# Adafruit_PyPortal_Pynt.net
KiCad netlist of a schematic drawn in EAGLE
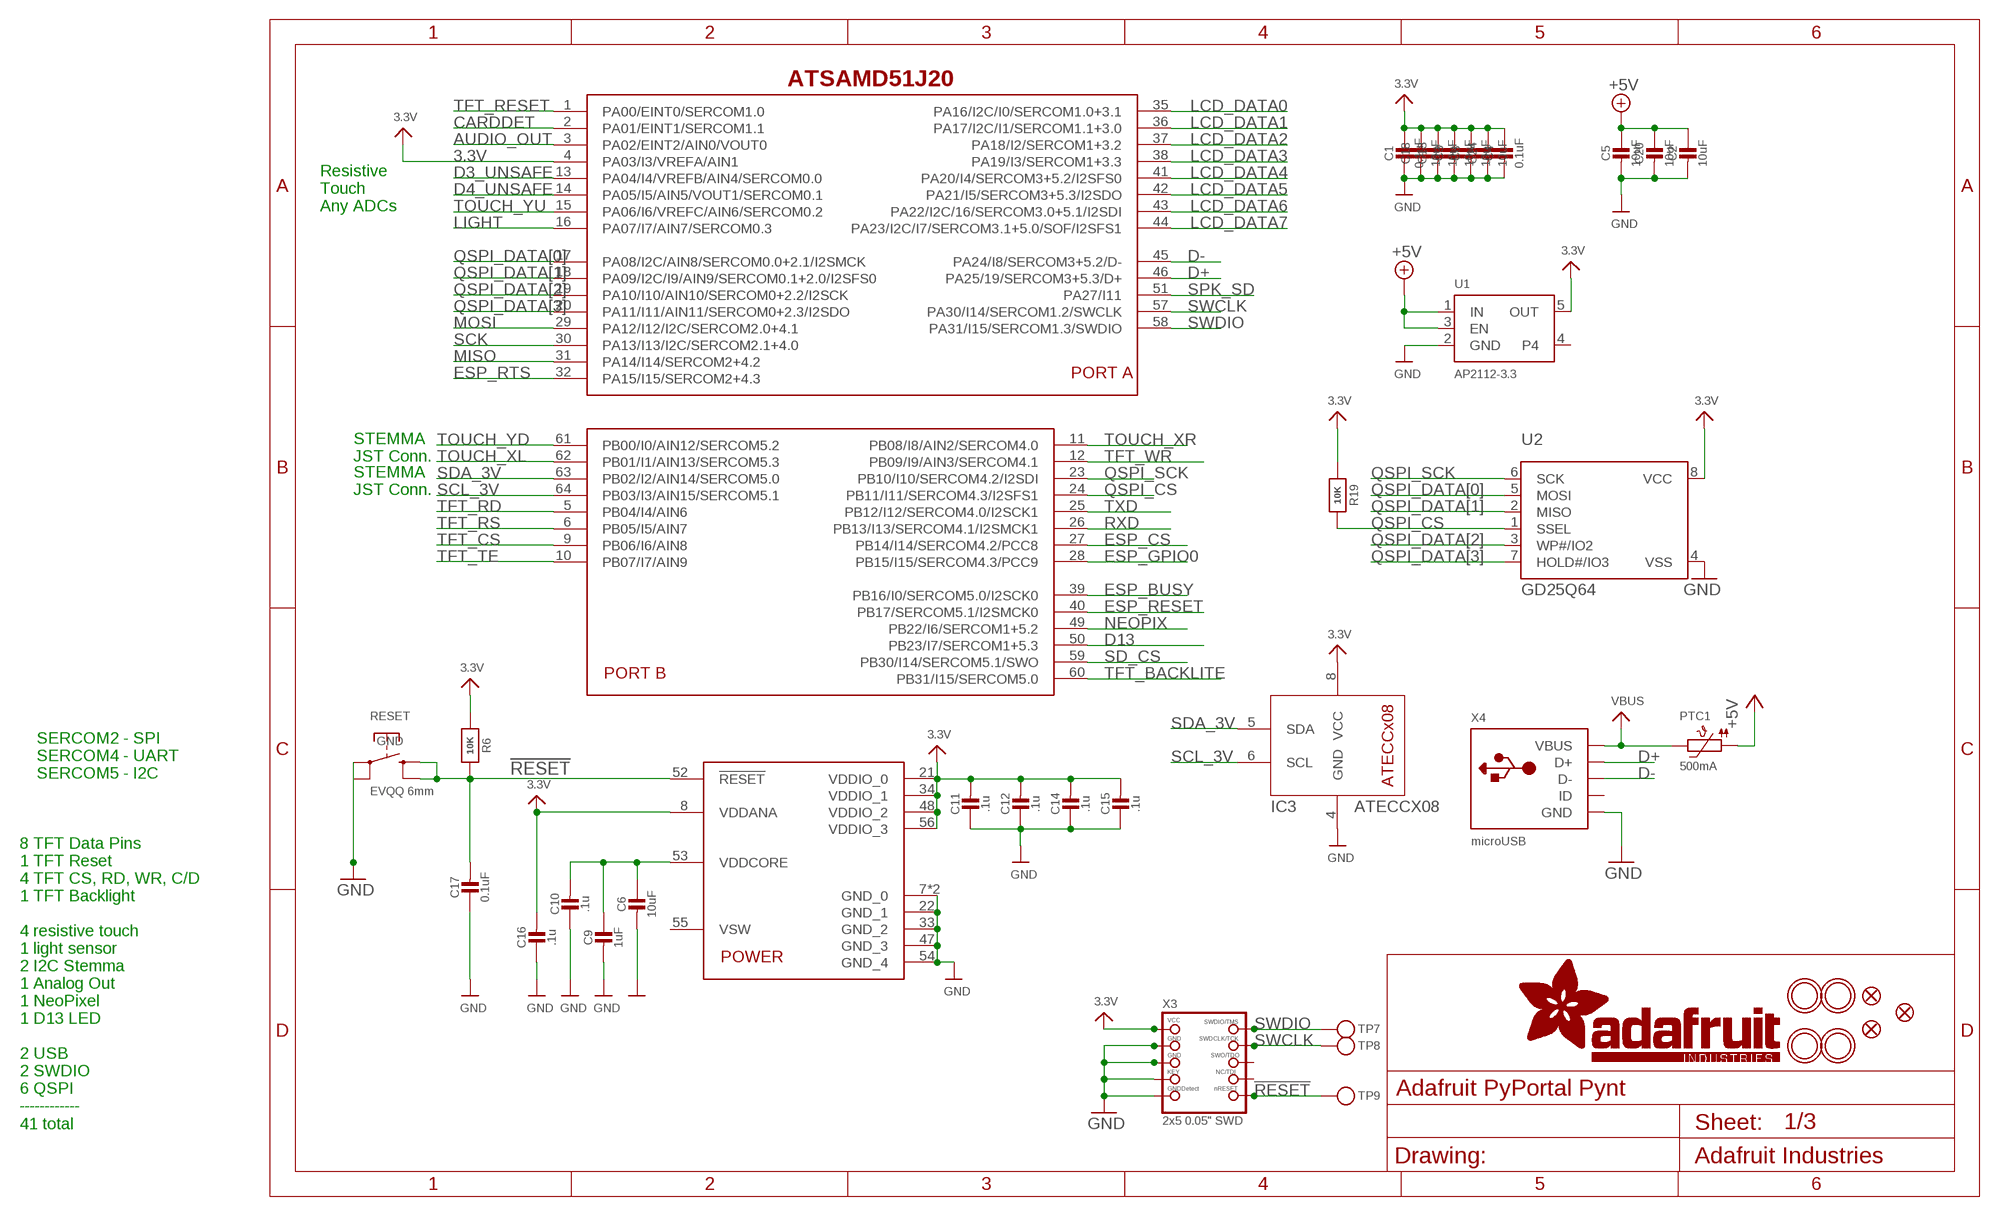
[diagram p0: schematic, sheet 1]
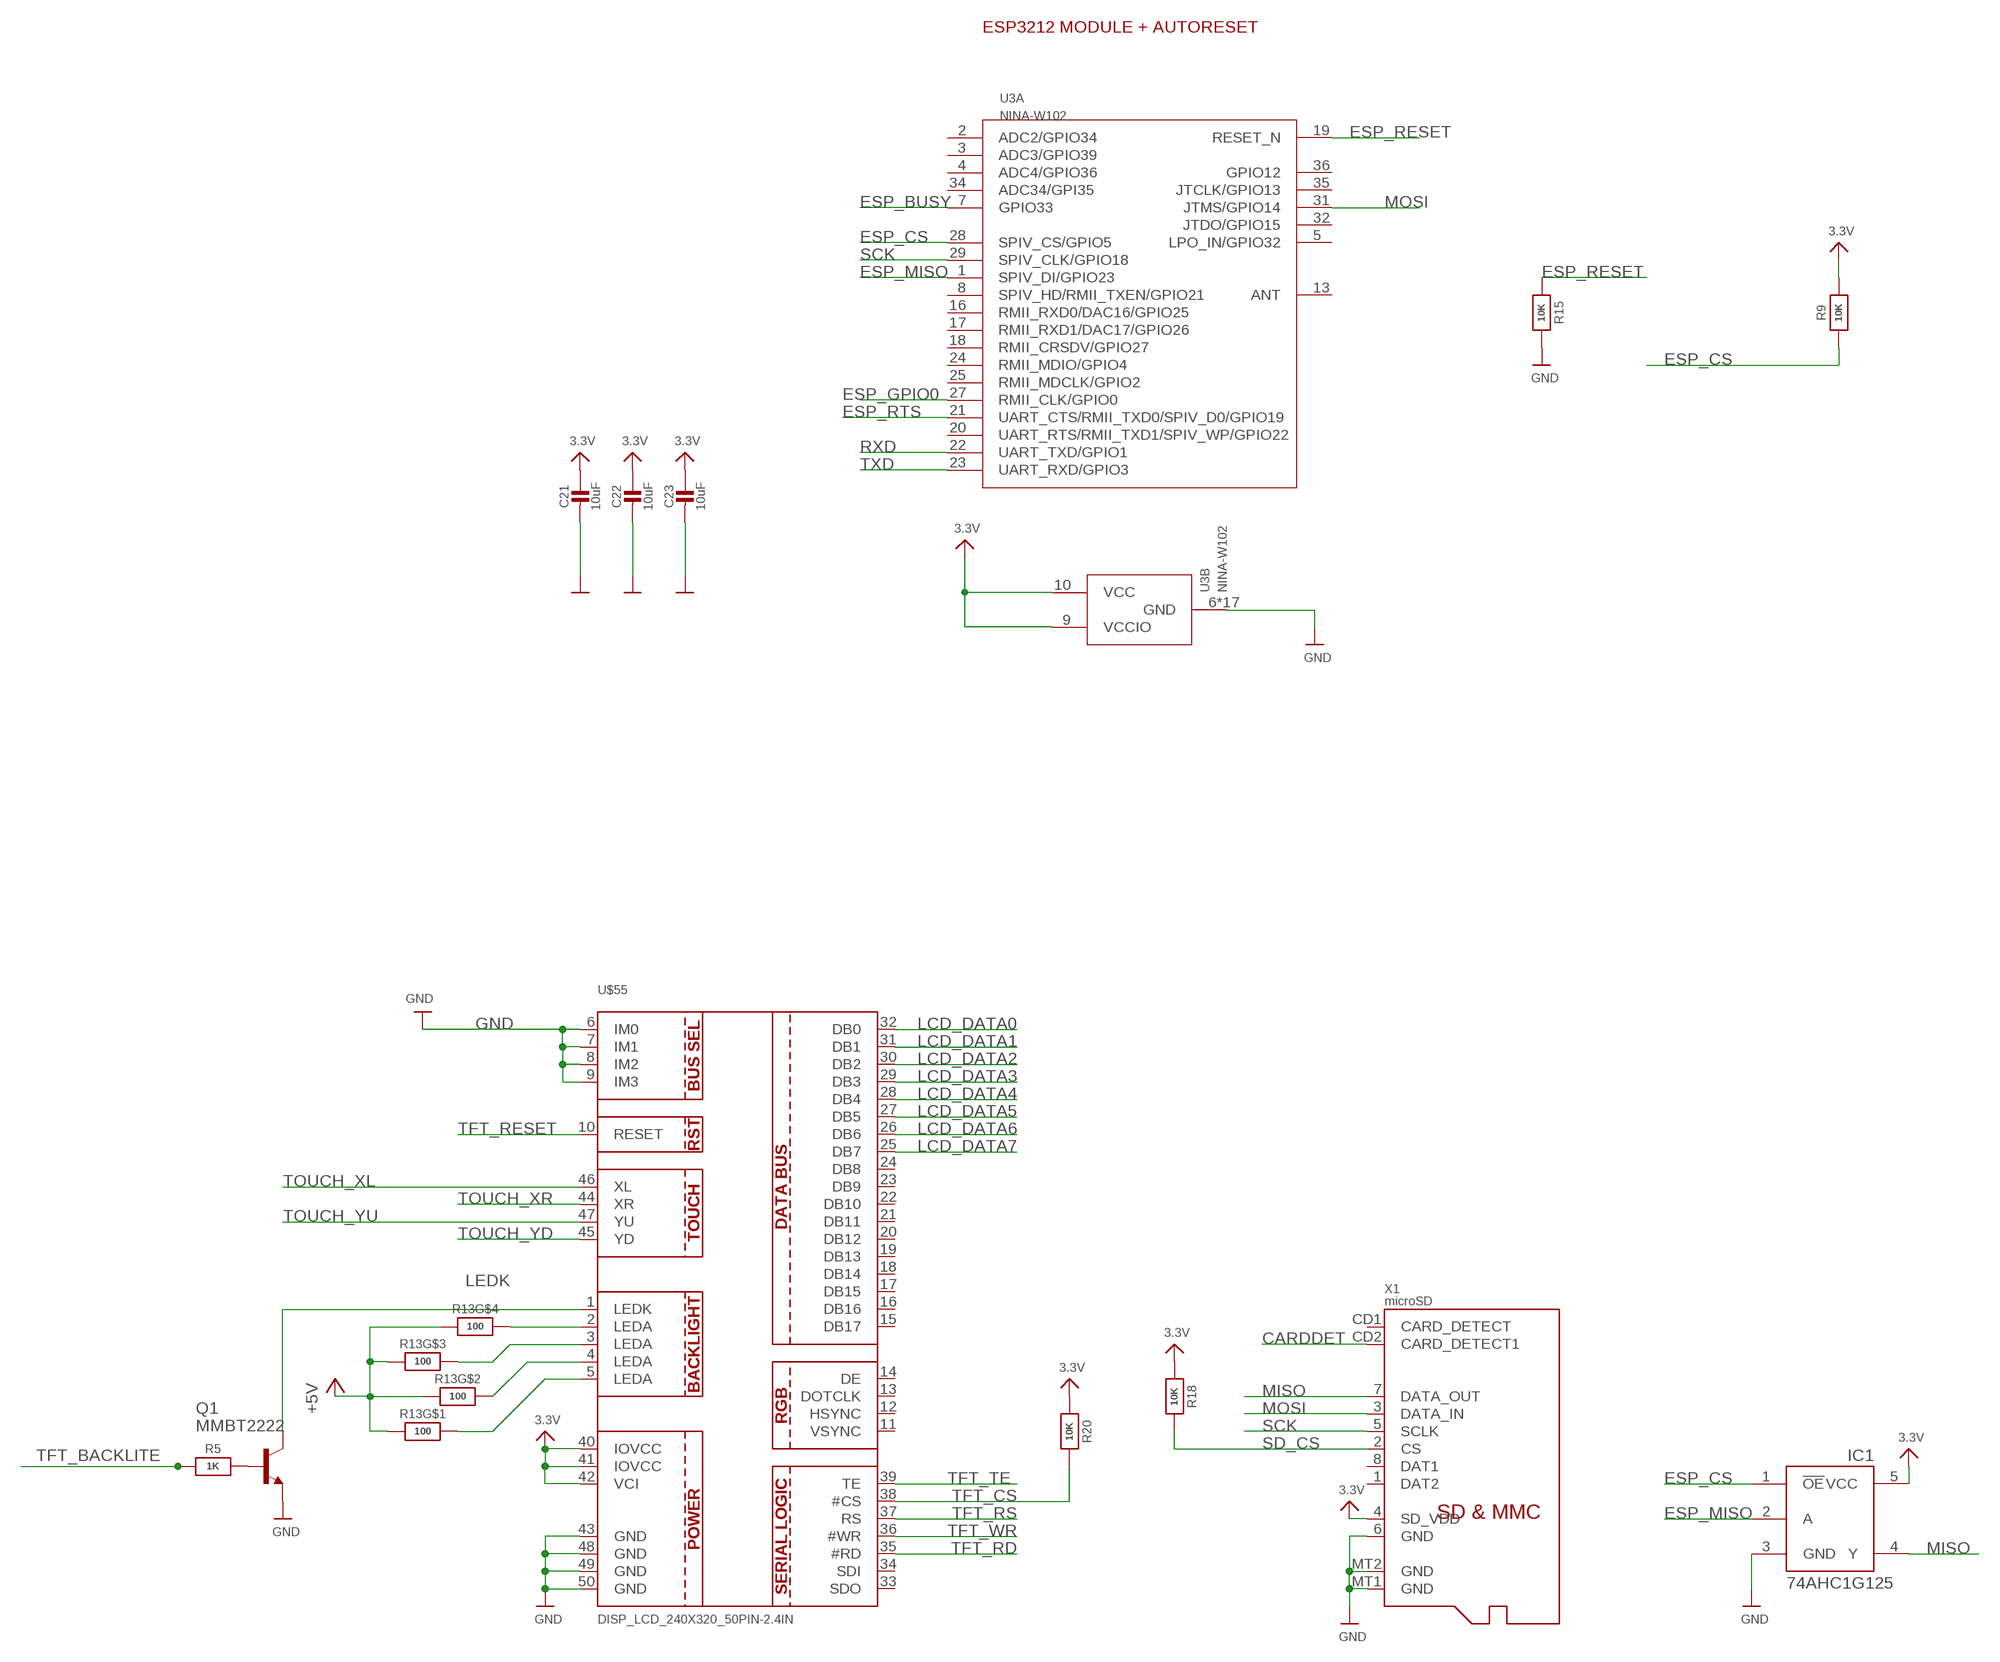
[diagram p1: schematic, sheet 2]
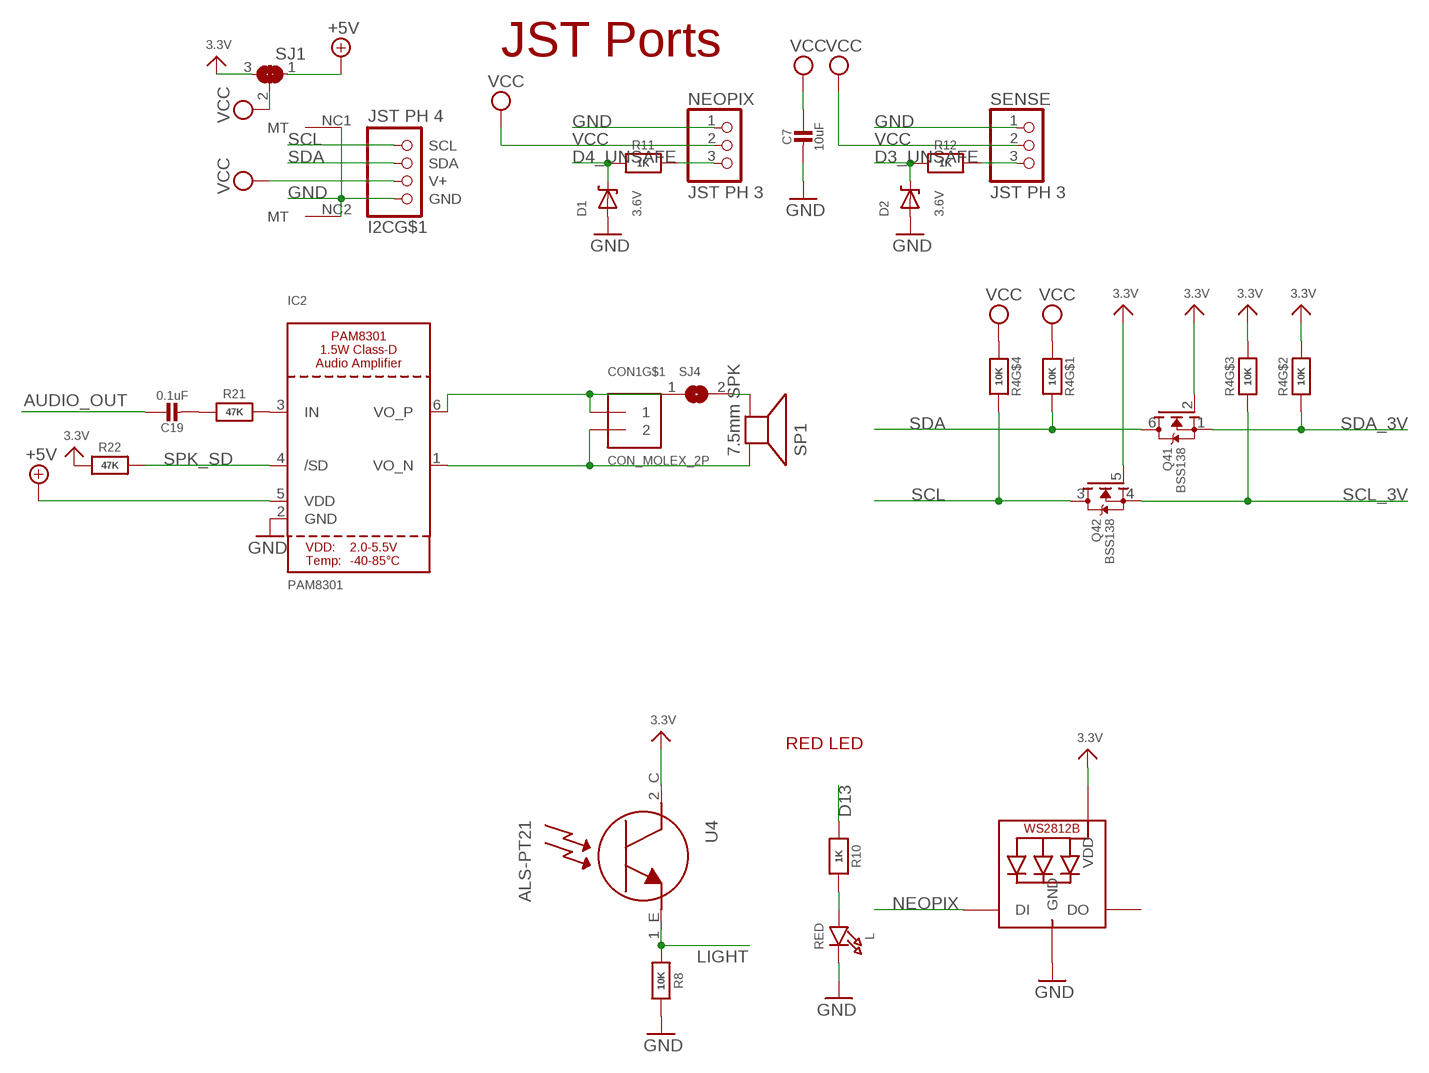
[diagram p2: schematic, sheet 3]

(export (version "E")
  (design (tool "Eeschema 10.0.6"))
  (components
    (comp (ref "C21")
      (value "10uF")
      (footprint "eagle-import:0805-NO")
      (libsource (lib "eagle-import") (part "CAP_CERAMIC0805-NOOUTLINE"))
    )
    (comp (ref "C22")
      (value "10uF")
      (footprint "eagle-import:0805-NO")
      (libsource (lib "eagle-import") (part "CAP_CERAMIC0805-NOOUTLINE"))
    )
    (comp (ref "C23")
      (value "10uF")
      (footprint "eagle-import:0805-NO")
      (libsource (lib "eagle-import") (part "CAP_CERAMIC0805-NOOUTLINE"))
    )
    (comp (ref "IC1")
      (value "74AHC1G125")
      (footprint "eagle-import:SOT23-5L")
      (libsource (lib "eagle-import") (part "74AHC1G125"))
    )
    (comp (ref "Q1")
      (value "MMBT2222")
      (footprint "eagle-import:SOT23-BEC")
      (libsource (lib "eagle-import") (part "-NPN-SOT23-BECMMBT2222ALT1"))
    )
    (comp (ref "R5")
      (value "1K")
      (footprint "eagle-import:0603-NO")
      (libsource (lib "eagle-import") (part "RESISTOR_0603_NOOUT"))
    )
    (comp (ref "R9")
      (value "10K")
      (footprint "eagle-import:0603-NO")
      (libsource (lib "eagle-import") (part "RESISTOR_0603_NOOUT"))
    )
    (comp (ref "R13")
      (value "100")
      (footprint "eagle-import:RESPACK_4X0603")
      (libsource (lib "eagle-import") (part "RESISTOR_4PACK"))
    )
    (comp (ref "R15")
      (value "10K")
      (footprint "eagle-import:0603-NO")
      (libsource (lib "eagle-import") (part "RESISTOR_0603_NOOUT"))
    )
    (comp (ref "R18")
      (value "10K")
      (footprint "eagle-import:0603-NO")
      (libsource (lib "eagle-import") (part "RESISTOR_0603_NOOUT"))
    )
    (comp (ref "R20")
      (value "10K")
      (footprint "eagle-import:0603-NO")
      (libsource (lib "eagle-import") (part "RESISTOR_0603_NOOUT"))
    )
    (comp (ref "U$55")
      (value "DISP_LCD_240X320_50PIN-2.4IN")
      (footprint "eagle-import:TFT_2.4IN_240X320_50PIN")
      (libsource (lib "eagle-import") (part "DISP_LCD_240X320_50PIN-2.4IN"))
    )
    (comp (ref "U3")
      (value "NINA-W102")
      (footprint "eagle-import:ARDUINO-UCS&SOCS_NINA-W1X")
      (fields (field (name "MANUFACTURER") "Ublocks"))
      (libsource (lib "eagle-import") (part "NINA-W10XNINA-W10X-102"))
    )
    (comp (ref "X1")
      (value "microSD")
      (footprint "eagle-import:MICROSD")
      (libsource (lib "eagle-import") (part "MICROSD"))
    )
    (comp (ref "C7")
      (value "10uF")
      (footprint "eagle-import:0805-NO")
      (libsource (lib "eagle-import") (part "CAP_CERAMIC0805-NOOUTLINE"))
    )
    (comp (ref "C19")
      (value "0.1uF")
      (footprint "eagle-import:0603-NO")
      (libsource (lib "eagle-import") (part "CAP_CERAMIC0603_NO"))
    )
    (comp (ref "CON1")
      (value "CON_MOLEX_2P")
      (footprint "eagle-import:53398-0271")
      (libsource (lib "eagle-import") (part "CON_MOLEX_2P"))
    )
    (comp (ref "D1")
      (value "3.6V")
      (footprint "eagle-import:SOD-323")
      (libsource (lib "eagle-import") (part "DIODE-ZENERSOD323"))
    )
    (comp (ref "D2")
      (value "3.6V")
      (footprint "eagle-import:SOD-323")
      (libsource (lib "eagle-import") (part "DIODE-ZENERSOD323"))
    )
    (comp (ref "I2C")
      (value "JST PH 4")
      (footprint "eagle-import:JSTPH4")
      (libsource (lib "eagle-import") (part "STEMMA_I2C_RASMT"))
    )
    (comp (ref "IC2")
      (value "PAM8301")
      (footprint "eagle-import:SOT23-6")
      (libsource (lib "eagle-import") (part "PAM8301"))
    )
    (comp (ref "L")
      (value "RED")
      (footprint "eagle-import:CHIPLED_0805_NOOUTLINE")
      (libsource (lib "eagle-import") (part "LED0805_NOOUTLINE"))
    )
    (comp (ref "LED1")
      (value "WS2812B3535")
      (footprint "eagle-import:LED3535")
      (libsource (lib "eagle-import") (part "WS2812B3535"))
    )
    (comp (ref "NEOPIX")
      (value "JST PH 3")
      (footprint "eagle-import:JSTPH3")
      (libsource (lib "eagle-import") (part "CON_JST_PH_3PIN"))
    )
    (comp (ref "Q4")
      (value "BSS138")
      (footprint "eagle-import:SOT363")
      (libsource (lib "eagle-import") (part "MOSFET-N_DUAL"))
    )
    (comp (ref "R4")
      (value "10K")
      (footprint "eagle-import:RESPACK_4X0603")
      (libsource (lib "eagle-import") (part "RESISTOR_4PACK"))
    )
    (comp (ref "R8")
      (value "10K")
      (footprint "eagle-import:0603-NO")
      (libsource (lib "eagle-import") (part "RESISTOR_0603_NOOUT"))
    )
    (comp (ref "R10")
      (value "1K")
      (footprint "eagle-import:0603-NO")
      (libsource (lib "eagle-import") (part "RESISTOR_0603_NOOUT"))
    )
    (comp (ref "R11")
      (value "1K")
      (footprint "eagle-import:0603-NO")
      (libsource (lib "eagle-import") (part "RESISTOR_0603_NOOUT"))
    )
    (comp (ref "R12")
      (value "1K")
      (footprint "eagle-import:0603-NO")
      (libsource (lib "eagle-import") (part "RESISTOR_0603_NOOUT"))
    )
    (comp (ref "R21")
      (value "47K")
      (footprint "eagle-import:0603-NO")
      (libsource (lib "eagle-import") (part "RESISTOR_0603_NOOUT"))
    )
    (comp (ref "R22")
      (value "47K")
      (footprint "eagle-import:0603-NO")
      (libsource (lib "eagle-import") (part "RESISTOR_0603_NOOUT"))
    )
    (comp (ref "SENSE")
      (value "JST PH 3")
      (footprint "eagle-import:JSTPH3")
      (libsource (lib "eagle-import") (part "CON_JST_PH_3PIN"))
    )
    (comp (ref "SJ1")
      (value "SOLDERJUMPER_2WAY")
      (footprint "eagle-import:SOLDERJUMPER_2WAY_OPEN_NOPASTE")
      (libsource (lib "eagle-import") (part "SOLDERJUMPER_2WAY"))
    )
    (comp (ref "SJ4")
      (value "SOLDERJUMPERCLOSED")
      (footprint "eagle-import:SOLDERJUMPER_CLOSEDWIRE")
      (libsource (lib "eagle-import") (part "SOLDERJUMPERCLOSED"))
    )
    (comp (ref "SP1")
      (value "7.5mm SPK")
      (footprint "eagle-import:BUZZER_SMT_7.5MM")
      (libsource (lib "eagle-import") (part "SPEAKER_7.5MM"))
    )
    (comp (ref "U4")
      (value "ALS-PT21")
      (footprint "eagle-import:ALS-PT26-21C")
      (libsource (lib "eagle-import") (part "PHOTOTRANSISTOR_PT26-21C"))
    )
    (comp (ref "C1")
      (value "0.1uF")
      (footprint "eagle-import:0603-NO")
      (libsource (lib "eagle-import") (part "CAP_CERAMIC0603_NO"))
    )
    (comp (ref "C2")
      (value "10uF")
      (footprint "eagle-import:0805-NO")
      (libsource (lib "eagle-import") (part "CAP_CERAMIC0805-NOOUTLINE"))
    )
    (comp (ref "C3")
      (value "10uF")
      (footprint "eagle-import:0805-NO")
      (libsource (lib "eagle-import") (part "CAP_CERAMIC0805-NOOUTLINE"))
    )
    (comp (ref "C4")
      (value "0.1uF")
      (footprint "eagle-import:0805-NO")
      (libsource (lib "eagle-import") (part "CAP_CERAMIC0805-NOOUTLINE"))
    )
    (comp (ref "C5")
      (value "10uF")
      (footprint "eagle-import:0805-NO")
      (libsource (lib "eagle-import") (part "CAP_CERAMIC0805-NOOUTLINE"))
    )
    (comp (ref "C6")
      (value "10uF")
      (footprint "eagle-import:0805-NO")
      (libsource (lib "eagle-import") (part "CAP_CERAMIC0805-NOOUTLINE"))
    )
    (comp (ref "C8")
      (value "10uF")
      (footprint "eagle-import:0805-NO")
      (libsource (lib "eagle-import") (part "CAP_CERAMIC0805-NOOUTLINE"))
    )
    (comp (ref "C9")
      (value "1uF")
      (footprint "eagle-import:0603-NO")
      (libsource (lib "eagle-import") (part "CAP_CERAMIC0603_NO"))
    )
    (comp (ref "C10")
      (value ".1u")
      (footprint "eagle-import:0603-NO")
      (libsource (lib "eagle-import") (part "CAP_CERAMIC0603_NO"))
    )
    (comp (ref "C11")
      (value ".1u")
      (footprint "eagle-import:0603-NO")
      (libsource (lib "eagle-import") (part "CAP_CERAMIC0603_NO"))
    )
    (comp (ref "C12")
      (value ".1u")
      (footprint "eagle-import:0603-NO")
      (libsource (lib "eagle-import") (part "CAP_CERAMIC0603_NO"))
    )
    (comp (ref "C13")
      (value "10uF")
      (footprint "eagle-import:0805-NO")
      (libsource (lib "eagle-import") (part "CAP_CERAMIC0805-NOOUTLINE"))
    )
    (comp (ref "C14")
      (value ".1u")
      (footprint "eagle-import:0603-NO")
      (libsource (lib "eagle-import") (part "CAP_CERAMIC0603_NO"))
    )
    (comp (ref "C15")
      (value ".1u")
      (footprint "eagle-import:0603-NO")
      (libsource (lib "eagle-import") (part "CAP_CERAMIC0603_NO"))
    )
    (comp (ref "C16")
      (value ".1u")
      (footprint "eagle-import:0603-NO")
      (libsource (lib "eagle-import") (part "CAP_CERAMIC0603_NO"))
    )
    (comp (ref "C17")
      (value "0.1uF")
      (footprint "eagle-import:0603-NO")
      (libsource (lib "eagle-import") (part "CAP_CERAMIC0603_NO"))
    )
    (comp (ref "C18")
      (value "10uF")
      (footprint "eagle-import:0805-NO")
      (libsource (lib "eagle-import") (part "CAP_CERAMIC0805-NOOUTLINE"))
    )
    (comp (ref "C20")
      (value "10uF")
      (footprint "eagle-import:0805-NO")
      (libsource (lib "eagle-import") (part "CAP_CERAMIC0805-NOOUTLINE"))
    )
    (comp (ref "C24")
      (value "10uF")
      (footprint "eagle-import:0805-NO")
      (libsource (lib "eagle-import") (part "CAP_CERAMIC0805-NOOUTLINE"))
    )
    (comp (ref "IC3")
      (value "ATECCX08")
      (footprint "eagle-import:SOIC8_150MIL")
      (libsource (lib "eagle-import") (part "ATECCX08"))
    )
    (comp (ref "PTC1")
      (value "500mA")
      (footprint "eagle-import:1206")
      (libsource (lib "eagle-import") (part "PTC1206"))
    )
    (comp (ref "R6")
      (value "10K")
      (footprint "eagle-import:0603-NO")
      (libsource (lib "eagle-import") (part "RESISTOR_0603_NOOUT"))
    )
    (comp (ref "R19")
      (value "10K")
      (footprint "eagle-import:0603-NO")
      (libsource (lib "eagle-import") (part "RESISTOR_0603_NOOUT"))
    )
    (comp (ref "RESET")
      (value "EVQQ 6mm")
      (footprint "eagle-import:EVQ-Q2_SMALLER")
      (libsource (lib "eagle-import") (part "SWITCH_TACT_SMT_EVQQ2_SMALL"))
    )
    (comp (ref "TP7")
      (value "TESTPOINTROUND1.5MM")
      (footprint "eagle-import:TESTPOINT_ROUND_1.5MM")
      (libsource (lib "eagle-import") (part "TESTPOINTROUND1.5MM"))
    )
    (comp (ref "TP8")
      (value "TESTPOINTROUND1.5MM")
      (footprint "eagle-import:TESTPOINT_ROUND_1.5MM")
      (libsource (lib "eagle-import") (part "TESTPOINTROUND1.5MM"))
    )
    (comp (ref "TP9")
      (value "TESTPOINTROUND1.5MM")
      (footprint "eagle-import:TESTPOINT_ROUND_1.5MM")
      (libsource (lib "eagle-import") (part "TESTPOINTROUND1.5MM"))
    )
    (comp (ref "U$2")
      (value "ATSAMD51J20")
      (footprint "eagle-import:PQFN64-1")
      (libsource (lib "eagle-import") (part "ATSAMD51J"))
    )
    (comp (ref "U$7")
      (value "MOUNTINGHOLE3.0THIN")
      (footprint "eagle-import:MOUNTINGHOLE_3.0_PLATEDTHIN")
      (libsource (lib "eagle-import") (part "MOUNTINGHOLE3.0THIN"))
    )
    (comp (ref "U$9")
      (value "FIDUCIAL_1MM")
      (footprint "eagle-import:FIDUCIAL_1MM")
      (libsource (lib "eagle-import") (part "FIDUCIAL_1MM"))
    )
    (comp (ref "U$11")
      (value "FIDUCIAL_1MM")
      (footprint "eagle-import:FIDUCIAL_1MM")
      (libsource (lib "eagle-import") (part "FIDUCIAL_1MM"))
    )
    (comp (ref "U$15")
      (value "MOUNTINGHOLE3.0THIN")
      (footprint "eagle-import:MOUNTINGHOLE_3.0_PLATEDTHIN")
      (libsource (lib "eagle-import") (part "MOUNTINGHOLE3.0THIN"))
    )
    (comp (ref "U$16")
      (value "MOUNTINGHOLE3.0THIN")
      (footprint "eagle-import:MOUNTINGHOLE_3.0_PLATEDTHIN")
      (libsource (lib "eagle-import") (part "MOUNTINGHOLE3.0THIN"))
    )
    (comp (ref "U$17")
      (value "MOUNTINGHOLE3.0THIN")
      (footprint "eagle-import:MOUNTINGHOLE_3.0_PLATEDTHIN")
      (libsource (lib "eagle-import") (part "MOUNTINGHOLE3.0THIN"))
    )
    (comp (ref "U$23")
      (value "FIDUCIAL_1MM")
      (footprint "eagle-import:FIDUCIAL_1MM")
      (libsource (lib "eagle-import") (part "FIDUCIAL_1MM"))
    )
    (comp (ref "U1")
      (value "AP2112-3.3")
      (footprint "eagle-import:SOT23-5")
      (libsource (lib "eagle-import") (part "VREG_SOT23-5"))
    )
    (comp (ref "U2")
      (value "GD25Q64")
      (footprint "eagle-import:SOIC8_208MIL")
      (libsource (lib "eagle-import") (part "SPIFLASH_8PIN208MIL"))
    )
    (comp (ref "X3")
      (value "2x5 0.05\" SWD")
      (footprint "eagle-import:2X05_1.27MM_SMT")
      (libsource (lib "eagle-import") (part "JTAG-CORTEX"))
    )
    (comp (ref "X4")
      (value "microUSB")
      (footprint "eagle-import:4UCONN_20329_NARROW")
      (libsource (lib "eagle-import") (part "USB_MICRO_NARROW"))
    )
  )
  (nets
    (net (code "1") (name "+5V") (class "Default")
      (node (ref "C2") (pin "1") (pinfunction "1_1") (pintype "passive"))
      (node (ref "C20") (pin "1") (pinfunction "1_1") (pintype "passive"))
      (node (ref "C5") (pin "1") (pinfunction "1_1") (pintype "passive"))
      (node (ref "IC2") (pin "5") (pinfunction "VDD_5") (pintype "power_in"))
      (node (ref "PTC1") (pin "1") (pinfunction "1_1") (pintype "passive"))
      (node (ref "R13") (pin "1") (pinfunction "1_1") (pintype "passive"))
      (node (ref "R13") (pin "2") (pinfunction "1_2") (pintype "passive"))
      (node (ref "R13") (pin "3") (pinfunction "1_3") (pintype "passive"))
      (node (ref "R13") (pin "4") (pinfunction "1_4") (pintype "passive"))
      (node (ref "SJ1") (pin "1") (pinfunction "1_1") (pintype "passive"))
      (node (ref "U1") (pin "1") (pinfunction "IN_1") (pintype "power_in"))
      (node (ref "U1") (pin "3") (pinfunction "EN_3") (pintype "input"))
    )
    (net (code "2") (name "3.3V") (class "Default")
      (node (ref "C1") (pin "1") (pinfunction "1_1") (pintype "passive"))
      (node (ref "C11") (pin "2") (pinfunction "2_2") (pintype "passive"))
      (node (ref "C12") (pin "2") (pinfunction "2_2") (pintype "passive"))
      (node (ref "C13") (pin "1") (pinfunction "1_1") (pintype "passive"))
      (node (ref "C14") (pin "2") (pinfunction "2_2") (pintype "passive"))
      (node (ref "C15") (pin "2") (pinfunction "2_2") (pintype "passive"))
      (node (ref "C16") (pin "2") (pinfunction "2_2") (pintype "passive"))
      (node (ref "C18") (pin "1") (pinfunction "1_1") (pintype "passive"))
      (node (ref "C21") (pin "1") (pinfunction "1_1") (pintype "passive"))
      (node (ref "C22") (pin "1") (pinfunction "1_1") (pintype "passive"))
      (node (ref "C23") (pin "1") (pinfunction "1_1") (pintype "passive"))
      (node (ref "C24") (pin "1") (pinfunction "1_1") (pintype "passive"))
      (node (ref "C3") (pin "1") (pinfunction "1_1") (pintype "passive"))
      (node (ref "C4") (pin "1") (pinfunction "1_1") (pintype "passive"))
      (node (ref "C8") (pin "1") (pinfunction "1_1") (pintype "passive"))
      (node (ref "IC1") (pin "5") (pinfunction "VCC_5") (pintype "power_in"))
      (node (ref "IC3") (pin "8") (pinfunction "VCC_8") (pintype "power_in"))
      (node (ref "LED1") (pin "2") (pinfunction "VDD_2") (pintype "power_in"))
      (node (ref "Q4") (pin "2") (pinfunction "G_2") (pintype "bidirectional"))
      (node (ref "Q4") (pin "5") (pinfunction "G_5") (pintype "bidirectional"))
      (node (ref "R18") (pin "1") (pinfunction "1_1") (pintype "passive"))
      (node (ref "R19") (pin "1") (pinfunction "1_1") (pintype "passive"))
      (node (ref "R20") (pin "1") (pinfunction "1_1") (pintype "passive"))
      (node (ref "R22") (pin "1") (pinfunction "1_1") (pintype "passive"))
      (node (ref "R4") (pin "2") (pinfunction "1_2") (pintype "passive"))
      (node (ref "R4") (pin "3") (pinfunction "1_3") (pintype "passive"))
      (node (ref "R6") (pin "1") (pinfunction "1_1") (pintype "passive"))
      (node (ref "R9") (pin "2") (pinfunction "2_2") (pintype "passive"))
      (node (ref "SJ1") (pin "3") (pinfunction "3_3") (pintype "passive"))
      (node (ref "U$2") (pin "21") (pinfunction "VDDIO_0_21") (pintype "bidirectional"))
      (node (ref "U$2") (pin "34") (pinfunction "VDDIO_1_34") (pintype "bidirectional"))
      (node (ref "U$2") (pin "4") (pinfunction "PA03/I3/VREFA/AIN1_4") (pintype "bidirectional"))
      (node (ref "U$2") (pin "48") (pinfunction "VDDIO_2_48") (pintype "bidirectional"))
      (node (ref "U$2") (pin "56") (pinfunction "VDDIO_3_56") (pintype "bidirectional"))
      (node (ref "U$2") (pin "8") (pinfunction "VDDANA_8") (pintype "bidirectional"))
      (node (ref "U$55") (pin "40") (pinfunction "IOVCC_40") (pintype "bidirectional"))
      (node (ref "U$55") (pin "41") (pinfunction "IOVCC_41") (pintype "bidirectional"))
      (node (ref "U$55") (pin "42") (pinfunction "VCI_42") (pintype "bidirectional"))
      (node (ref "U1") (pin "5") (pinfunction "OUT_5") (pintype "power_in"))
      (node (ref "U2") (pin "8") (pinfunction "VCC_8") (pintype "bidirectional"))
      (node (ref "U3") (pin "10") (pinfunction "VCC_10") (pintype "bidirectional"))
      (node (ref "U3") (pin "9") (pinfunction "VCCIO_9") (pintype "bidirectional"))
      (node (ref "U4") (pin "2_C") (pinfunction "C_2_C") (pintype "bidirectional"))
      (node (ref "X1") (pin "4") (pinfunction "SD_VDD_4") (pintype "power_in"))
      (node (ref "X3") (pin "1") (pinfunction "VCC_1") (pintype "power_in"))
    )
    (net (code "3") (name "AUDIO_OUT") (class "Default")
      (node (ref "C19") (pin "1") (pinfunction "1_1") (pintype "passive"))
      (node (ref "U$2") (pin "3") (pinfunction "PA02/EINT2/AIN0/VOUT0_3") (pintype "bidirectional"))
    )
    (net (code "4") (name "CARDDET") (class "Default")
      (node (ref "U$2") (pin "2") (pinfunction "PA01/EINT1/SERCOM1.1_2") (pintype "bidirectional"))
      (node (ref "X1") (pin "CD2") (pinfunction "CARD_DETECT1_CD2") (pintype "passive"))
    )
    (net (code "5") (name "D+") (class "Default")
      (node (ref "U$2") (pin "46") (pinfunction "PA25/19/SERCOM3+5.3/D+_46") (pintype "bidirectional"))
      (node (ref "X4") (pin "D+") (pinfunction "D+_D+") (pintype "bidirectional"))
    )
    (net (code "6") (name "D-") (class "Default")
      (node (ref "U$2") (pin "45") (pinfunction "PA24/I8/SERCOM3+5.2/D-_45") (pintype "bidirectional"))
      (node (ref "X4") (pin "D-") (pinfunction "D-_D-") (pintype "bidirectional"))
    )
    (net (code "7") (name "D3_UNSAFE") (class "Default")
      (node (ref "D2") (pin "C") (pinfunction "C_C") (pintype "passive"))
      (node (ref "R12") (pin "2") (pinfunction "2_2") (pintype "passive"))
      (node (ref "U$2") (pin "13") (pinfunction "PA04/I4/VREFB/AIN4/SERCOM0.0_13") (pintype "bidirectional"))
    )
    (net (code "8") (name "D4_UNSAFE") (class "Default")
      (node (ref "D1") (pin "C") (pinfunction "C_C") (pintype "passive"))
      (node (ref "R11") (pin "2") (pinfunction "2_2") (pintype "passive"))
      (node (ref "U$2") (pin "14") (pinfunction "PA05/I5/AIN5/VOUT1/SERCOM0.1_14") (pintype "bidirectional"))
    )
    (net (code "9") (name "D13") (class "Default")
      (node (ref "R10") (pin "1") (pinfunction "1_1") (pintype "passive"))
      (node (ref "U$2") (pin "50") (pinfunction "PB23/I7/SERCOM1+5.3_50") (pintype "bidirectional"))
    )
    (net (code "10") (name "ESP_BUSY") (class "Default")
      (node (ref "U$2") (pin "39") (pinfunction "PB16/I0/SERCOM5.0/I2SCK0_39") (pintype "bidirectional"))
      (node (ref "U3") (pin "7") (pinfunction "GPIO33_7") (pintype "bidirectional"))
    )
    (net (code "11") (name "ESP_CS") (class "Default")
      (node (ref "IC1") (pin "1") (pinfunction "~{OE}_1") (pintype "input"))
      (node (ref "R9") (pin "1") (pinfunction "1_1") (pintype "passive"))
      (node (ref "U$2") (pin "27") (pinfunction "PB14/I14/SERCOM4.2/PCC8_27") (pintype "bidirectional"))
      (node (ref "U3") (pin "28") (pinfunction "SPIV_CS/GPIO5_28") (pintype "bidirectional"))
    )
    (net (code "12") (name "ESP_GPIO0") (class "Default")
      (node (ref "U$2") (pin "28") (pinfunction "PB15/I15/SERCOM4.3/PCC9_28") (pintype "bidirectional"))
      (node (ref "U3") (pin "27") (pinfunction "RMII_CLK/GPIO0_27") (pintype "bidirectional"))
    )
    (net (code "13") (name "ESP_MISO") (class "Default")
      (node (ref "IC1") (pin "2") (pinfunction "A_2") (pintype "input"))
      (node (ref "U3") (pin "1") (pinfunction "SPIV_DI/GPIO23_1") (pintype "bidirectional"))
    )
    (net (code "14") (name "ESP_RESET") (class "Default")
      (node (ref "R15") (pin "1") (pinfunction "1_1") (pintype "passive"))
      (node (ref "U$2") (pin "40") (pinfunction "PB17/SERCOM5.1/I2SMCK0_40") (pintype "bidirectional"))
      (node (ref "U3") (pin "19") (pinfunction "RESET_N_19") (pintype "bidirectional"))
    )
    (net (code "15") (name "ESP_RTS") (class "Default")
      (node (ref "U$2") (pin "32") (pinfunction "PA15/I15/SERCOM2+4.3_32") (pintype "bidirectional"))
      (node (ref "U3") (pin "21") (pinfunction "UART_CTS/RMII_TXD0/SPIV_D0/GPIO19_21") (pintype "bidirectional"))
    )
    (net (code "16") (name "GND") (class "Default")
      (node (ref "C1") (pin "2") (pinfunction "2_2") (pintype "passive"))
      (node (ref "C10") (pin "1") (pinfunction "1_1") (pintype "passive"))
      (node (ref "C11") (pin "1") (pinfunction "1_1") (pintype "passive"))
      (node (ref "C12") (pin "1") (pinfunction "1_1") (pintype "passive"))
      (node (ref "C13") (pin "2") (pinfunction "2_2") (pintype "passive"))
      (node (ref "C14") (pin "1") (pinfunction "1_1") (pintype "passive"))
      (node (ref "C15") (pin "1") (pinfunction "1_1") (pintype "passive"))
      (node (ref "C16") (pin "1") (pinfunction "1_1") (pintype "passive"))
      (node (ref "C17") (pin "1") (pinfunction "1_1") (pintype "passive"))
      (node (ref "C18") (pin "2") (pinfunction "2_2") (pintype "passive"))
      (node (ref "C2") (pin "2") (pinfunction "2_2") (pintype "passive"))
      (node (ref "C20") (pin "2") (pinfunction "2_2") (pintype "passive"))
      (node (ref "C21") (pin "2") (pinfunction "2_2") (pintype "passive"))
      (node (ref "C22") (pin "2") (pinfunction "2_2") (pintype "passive"))
      (node (ref "C23") (pin "2") (pinfunction "2_2") (pintype "passive"))
      (node (ref "C24") (pin "2") (pinfunction "2_2") (pintype "passive"))
      (node (ref "C3") (pin "2") (pinfunction "2_2") (pintype "passive"))
      (node (ref "C4") (pin "2") (pinfunction "2_2") (pintype "passive"))
      (node (ref "C5") (pin "2") (pinfunction "2_2") (pintype "passive"))
      (node (ref "C6") (pin "2") (pinfunction "2_2") (pintype "passive"))
      (node (ref "C7") (pin "2") (pinfunction "2_2") (pintype "passive"))
      (node (ref "C8") (pin "2") (pinfunction "2_2") (pintype "passive"))
      (node (ref "C9") (pin "2") (pinfunction "2_2") (pintype "passive"))
      (node (ref "D1") (pin "A") (pinfunction "A_A") (pintype "passive"))
      (node (ref "D2") (pin "A") (pinfunction "A_A") (pintype "passive"))
      (node (ref "I2C") (pin "1") (pinfunction "GND_1") (pintype "passive"))
      (node (ref "I2C") (pin "NC1") (pinfunction "MT_NC1") (pintype "bidirectional"))
      (node (ref "I2C") (pin "NC2") (pinfunction "MT_NC2") (pintype "bidirectional"))
      (node (ref "IC1") (pin "3") (pinfunction "GND_3") (pintype "power_in"))
      (node (ref "IC2") (pin "2") (pinfunction "GND_2") (pintype "power_in"))
      (node (ref "IC3") (pin "4") (pinfunction "GND_4") (pintype "power_in"))
      (node (ref "L") (pin "C") (pinfunction "C_C") (pintype "passive"))
      (node (ref "LED1") (pin "4") (pinfunction "GND_4") (pintype "power_in"))
      (node (ref "NEOPIX") (pin "1") (pinfunction "1_1") (pintype "passive"))
      (node (ref "Q1") (pin "E") (pinfunction "E_E") (pintype "passive"))
      (node (ref "R15") (pin "2") (pinfunction "2_2") (pintype "passive"))
      (node (ref "R8") (pin "1") (pinfunction "1_1") (pintype "passive"))
      (node (ref "RESET") (pin "A") (pinfunction "P_A") (pintype "passive"))
      (node (ref "RESET") (pin "A'") (pinfunction "P1_A'") (pintype "passive"))
      (node (ref "SENSE") (pin "1") (pinfunction "1_1") (pintype "passive"))
      (node (ref "U$2") (pin "22") (pinfunction "GND_1_22") (pintype "bidirectional"))
      (node (ref "U$2") (pin "33") (pinfunction "GND_2_33") (pintype "bidirectional"))
      (node (ref "U$2") (pin "47") (pinfunction "GND_3_47") (pintype "bidirectional"))
      (node (ref "U$2") (pin "54") (pinfunction "GND_4_54") (pintype "bidirectional"))
      (node (ref "U$2") (pin "7") (pinfunction "GND_0_7") (pintype "bidirectional"))
      (node (ref "U$2") (pin "EXP") (pinfunction "GND_0_EXP") (pintype "bidirectional"))
      (node (ref "U$55") (pin "43") (pinfunction "GND_43") (pintype "bidirectional"))
      (node (ref "U$55") (pin "48") (pinfunction "GND_48") (pintype "bidirectional"))
      (node (ref "U$55") (pin "49") (pinfunction "GND_49") (pintype "bidirectional"))
      (node (ref "U$55") (pin "50") (pinfunction "GND_50") (pintype "bidirectional"))
      (node (ref "U$55") (pin "6") (pinfunction "IM0_6") (pintype "bidirectional"))
      (node (ref "U$55") (pin "7") (pinfunction "IM1_7") (pintype "bidirectional"))
      (node (ref "U$55") (pin "8") (pinfunction "IM2_8") (pintype "bidirectional"))
      (node (ref "U$55") (pin "9") (pinfunction "IM3_9") (pintype "bidirectional"))
      (node (ref "U1") (pin "2") (pinfunction "GND_2") (pintype "power_in"))
      (node (ref "U2") (pin "4") (pinfunction "VSS_4") (pintype "bidirectional"))
      (node (ref "U3") (pin "12") (pinfunction "GND_12") (pintype "bidirectional"))
      (node (ref "U3") (pin "14") (pinfunction "GND_14") (pintype "bidirectional"))
      (node (ref "U3") (pin "26") (pinfunction "GND_26") (pintype "bidirectional"))
      (node (ref "U3") (pin "30") (pinfunction "GND_30") (pintype "bidirectional"))
      (node (ref "U3") (pin "6") (pinfunction "GND_6") (pintype "bidirectional"))
      (node (ref "U3") (pin "GND@1") (pinfunction "GND_GND@1") (pintype "bidirectional"))
      (node (ref "U3") (pin "GND@10") (pinfunction "GND_GND@10") (pintype "bidirectional"))
      (node (ref "U3") (pin "GND@11") (pinfunction "GND_GND@11") (pintype "bidirectional"))
      (node (ref "U3") (pin "GND@12") (pinfunction "GND_GND@12") (pintype "bidirectional"))
      (node (ref "U3") (pin "GND@2") (pinfunction "GND_GND@2") (pintype "bidirectional"))
      (node (ref "U3") (pin "GND@3") (pinfunction "GND_GND@3") (pintype "bidirectional"))
      (node (ref "U3") (pin "GND@4") (pinfunction "GND_GND@4") (pintype "bidirectional"))
      (node (ref "U3") (pin "GND@5") (pinfunction "GND_GND@5") (pintype "bidirectional"))
      (node (ref "U3") (pin "GND@6") (pinfunction "GND_GND@6") (pintype "bidirectional"))
      (node (ref "U3") (pin "GND@7") (pinfunction "GND_GND@7") (pintype "bidirectional"))
      (node (ref "U3") (pin "GND@8") (pinfunction "GND_GND@8") (pintype "bidirectional"))
      (node (ref "U3") (pin "GND@9") (pinfunction "GND_GND@9") (pintype "bidirectional"))
      (node (ref "X1") (pin "6") (pinfunction "GND_6") (pintype "power_in"))
      (node (ref "X1") (pin "MT1") (pinfunction "GND_MT1") (pintype "power_in"))
      (node (ref "X1") (pin "MT2") (pinfunction "GND_MT2") (pintype "power_in"))
      (node (ref "X3") (pin "3") (pinfunction "GND_3") (pintype "power_in"))
      (node (ref "X3") (pin "5") (pinfunction "GND_5") (pintype "power_in"))
      (node (ref "X3") (pin "7") (pinfunction "KEY_7") (pintype "bidirectional"))
      (node (ref "X3") (pin "9") (pinfunction "GNDDETECT_9") (pintype "bidirectional"))
      (node (ref "X4") (pin "BASE@1") (pinfunction "GND_BASE@1") (pintype "power_in"))
      (node (ref "X4") (pin "BASE@2") (pinfunction "GND_BASE@2") (pintype "power_in"))
      (node (ref "X4") (pin "GND") (pinfunction "GND_GND") (pintype "power_in"))
      (node (ref "X4") (pin "SPRT@1") (pinfunction "GND_SPRT@1") (pintype "power_in"))
      (node (ref "X4") (pin "SPRT@2") (pinfunction "GND_SPRT@2") (pintype "power_in"))
      (node (ref "X4") (pin "SPRT@3") (pinfunction "GND_SPRT@3") (pintype "power_in"))
      (node (ref "X4") (pin "SPRT@4") (pinfunction "GND_SPRT@4") (pintype "power_in"))
    )
    (net (code "17") (name "LCD_DATA0") (class "Default")
      (node (ref "U$2") (pin "35") (pinfunction "PA16/I2C/I0/SERCOM1.0+3.1_35") (pintype "bidirectional"))
      (node (ref "U$55") (pin "32") (pinfunction "DB0_32") (pintype "bidirectional"))
    )
    (net (code "18") (name "LCD_DATA1") (class "Default")
      (node (ref "U$2") (pin "36") (pinfunction "PA17/I2C/I1/SERCOM1.1+3.0_36") (pintype "bidirectional"))
      (node (ref "U$55") (pin "31") (pinfunction "DB1_31") (pintype "bidirectional"))
    )
    (net (code "19") (name "LCD_DATA2") (class "Default")
      (node (ref "U$2") (pin "37") (pinfunction "PA18/I2/SERCOM1+3.2_37") (pintype "bidirectional"))
      (node (ref "U$55") (pin "30") (pinfunction "DB2_30") (pintype "bidirectional"))
    )
    (net (code "20") (name "LCD_DATA3") (class "Default")
      (node (ref "U$2") (pin "38") (pinfunction "PA19/I3/SERCOM1+3.3_38") (pintype "bidirectional"))
      (node (ref "U$55") (pin "29") (pinfunction "DB3_29") (pintype "bidirectional"))
    )
    (net (code "21") (name "LCD_DATA4") (class "Default")
      (node (ref "U$2") (pin "41") (pinfunction "PA20/I4/SERCOM3+5.2/I2SFS0_41") (pintype "bidirectional"))
      (node (ref "U$55") (pin "28") (pinfunction "DB4_28") (pintype "bidirectional"))
    )
    (net (code "22") (name "LCD_DATA5") (class "Default")
      (node (ref "U$2") (pin "42") (pinfunction "PA21/I5/SERCOM3+5.3/I2SDO_42") (pintype "bidirectional"))
      (node (ref "U$55") (pin "27") (pinfunction "DB5_27") (pintype "bidirectional"))
    )
    (net (code "23") (name "LCD_DATA6") (class "Default")
      (node (ref "U$2") (pin "43") (pinfunction "PA22/I2C/16/SERCOM3.0+5.1/I2SDI_43") (pintype "bidirectional"))
      (node (ref "U$55") (pin "26") (pinfunction "DB6_26") (pintype "bidirectional"))
    )
    (net (code "24") (name "LCD_DATA7") (class "Default")
      (node (ref "U$2") (pin "44") (pinfunction "PA23/I2C/I7/SERCOM3.1+5.0/SOF/I2SFS1_44") (pintype "bidirectional"))
      (node (ref "U$55") (pin "25") (pinfunction "DB7_25") (pintype "bidirectional"))
    )
    (net (code "25") (name "LEDK") (class "Default")
      (node (ref "Q1") (pin "C") (pinfunction "C_C") (pintype "passive"))
      (node (ref "U$55") (pin "1") (pinfunction "LEDK_1") (pintype "bidirectional"))
    )
    (net (code "26") (name "LIGHT") (class "Default")
      (node (ref "R8") (pin "2") (pinfunction "2_2") (pintype "passive"))
      (node (ref "U$2") (pin "16") (pinfunction "PA07/I7/AIN7/SERCOM0.3_16") (pintype "bidirectional"))
      (node (ref "U4") (pin "1_E") (pinfunction "E_1_E") (pintype "bidirectional"))
    )
    (net (code "27") (name "MISO") (class "Default")
      (node (ref "IC1") (pin "4") (pinfunction "Y_4") (pintype "output"))
      (node (ref "U$2") (pin "31") (pinfunction "PA14/I14/SERCOM2+4.2_31") (pintype "bidirectional"))
      (node (ref "X1") (pin "7") (pinfunction "DATA_OUT_7") (pintype "output"))
    )
    (net (code "28") (name "MOSI") (class "Default")
      (node (ref "U$2") (pin "29") (pinfunction "PA12/I12/I2C/SERCOM2.0+4.1_29") (pintype "bidirectional"))
      (node (ref "U3") (pin "31") (pinfunction "JTMS/GPIO14_31") (pintype "bidirectional"))
      (node (ref "X1") (pin "3") (pinfunction "DATA_IN_3") (pintype "input"))
    )
    (net (code "29") (name "NEOPIX") (class "Default")
      (node (ref "LED1") (pin "1") (pinfunction "DI_1") (pintype "input"))
      (node (ref "U$2") (pin "49") (pinfunction "PB22/I6/SERCOM1+5.2_49") (pintype "bidirectional"))
    )
    (net (code "30") (name "Net-(C19-Pad2)") (class "Default")
      (node (ref "C19") (pin "2") (pinfunction "2_2") (pintype "passive"))
      (node (ref "R21") (pin "1") (pinfunction "1_1") (pintype "passive"))
    )
    (net (code "31") (name "Net-(IC2-IN)") (class "Default")
      (node (ref "IC2") (pin "3") (pinfunction "IN_3") (pintype "input"))
      (node (ref "R21") (pin "2") (pinfunction "2_2") (pintype "passive"))
    )
    (net (code "32") (name "Net-(IC2-VO_N)") (class "Default")
      (node (ref "CON1") (pin "2") (pinfunction "2_2") (pintype "passive"))
      (node (ref "IC2") (pin "1") (pinfunction "VO_N_1") (pintype "output"))
      (node (ref "SP1") (pin "+") (pinfunction "+_+") (pintype "passive"))
    )
    (net (code "33") (name "Net-(IC2-VO_P)") (class "Default")
      (node (ref "CON1") (pin "1") (pinfunction "1_1") (pintype "passive"))
      (node (ref "IC2") (pin "6") (pinfunction "VO_P_6") (pintype "output"))
      (node (ref "SJ4") (pin "1") (pinfunction "1_1") (pintype "passive"))
    )
    (net (code "34") (name "Net-(L-PadA)") (class "Default")
      (node (ref "L") (pin "A") (pinfunction "A_A") (pintype "passive"))
      (node (ref "R10") (pin "2") (pinfunction "2_2") (pintype "passive"))
    )
    (net (code "35") (name "Net-(NEOPIX-Pad3)") (class "Default")
      (node (ref "NEOPIX") (pin "3") (pinfunction "3_3") (pintype "passive"))
      (node (ref "R11") (pin "1") (pinfunction "1_1") (pintype "passive"))
    )
    (net (code "36") (name "Net-(Q1-PadB)") (class "Default")
      (node (ref "Q1") (pin "B") (pinfunction "B_B") (pintype "passive"))
      (node (ref "R5") (pin "2") (pinfunction "2_2") (pintype "passive"))
    )
    (net (code "37") (name "Net-(R12-Pad1)") (class "Default")
      (node (ref "R12") (pin "1") (pinfunction "1_1") (pintype "passive"))
      (node (ref "SENSE") (pin "3") (pinfunction "3_3") (pintype "passive"))
    )
    (net (code "38") (name "Net-(R13A-2)") (class "Default")
      (node (ref "R13") (pin "8") (pinfunction "2_8") (pintype "passive"))
      (node (ref "U$55") (pin "5") (pinfunction "LEDA_5") (pintype "bidirectional"))
    )
    (net (code "39") (name "Net-(R13B-2)") (class "Default")
      (node (ref "R13") (pin "7") (pinfunction "2_7") (pintype "passive"))
      (node (ref "U$55") (pin "4") (pinfunction "LEDA_4") (pintype "bidirectional"))
    )
    (net (code "40") (name "Net-(R13C-2)") (class "Default")
      (node (ref "R13") (pin "6") (pinfunction "2_6") (pintype "passive"))
      (node (ref "U$55") (pin "3") (pinfunction "LEDA_3") (pintype "bidirectional"))
    )
    (net (code "41") (name "Net-(R13D-2)") (class "Default")
      (node (ref "R13") (pin "5") (pinfunction "2_5") (pintype "passive"))
      (node (ref "U$55") (pin "2") (pinfunction "LEDA_2") (pintype "bidirectional"))
    )
    (net (code "42") (name "Net-(SJ4-Pad2)") (class "Default")
      (node (ref "SJ4") (pin "2") (pinfunction "2_2") (pintype "passive"))
      (node (ref "SP1") (pin "-") (pinfunction "-_-") (pintype "passive"))
    )
    (net (code "43") (name "Net-(U$2C-VDDCORE)") (class "Default")
      (node (ref "C10") (pin "2") (pinfunction "2_2") (pintype "passive"))
      (node (ref "C6") (pin "1") (pinfunction "1_1") (pintype "passive"))
      (node (ref "C9") (pin "1") (pinfunction "1_1") (pintype "passive"))
      (node (ref "U$2") (pin "53") (pinfunction "VDDCORE_53") (pintype "bidirectional"))
    )
    (net (code "44") (name "QSPI_CS") (class "Default")
      (node (ref "R19") (pin "2") (pinfunction "2_2") (pintype "passive"))
      (node (ref "U$2") (pin "24") (pinfunction "PB11/I11/SERCOM4.3/I2SFS1_24") (pintype "bidirectional"))
      (node (ref "U2") (pin "1") (pinfunction "SSEL_1") (pintype "bidirectional"))
    )
    (net (code "45") (name "QSPI_DATA[0]") (class "Default")
      (node (ref "U$2") (pin "17") (pinfunction "PA08/I2C/AIN8/SERCOM0.0+2.1/I2SMCK_17") (pintype "bidirectional"))
      (node (ref "U2") (pin "5") (pinfunction "MOSI_5") (pintype "bidirectional"))
    )
    (net (code "46") (name "QSPI_DATA[1]") (class "Default")
      (node (ref "U$2") (pin "18") (pinfunction "PA09/I2C/I9/AIN9/SERCOM0.1+2.0/I2SFS0_18") (pintype "bidirectional"))
      (node (ref "U2") (pin "2") (pinfunction "MISO_2") (pintype "bidirectional"))
    )
    (net (code "47") (name "QSPI_DATA[2]") (class "Default")
      (node (ref "U$2") (pin "19") (pinfunction "PA10/I10/AIN10/SERCOM0+2.2/I2SCK_19") (pintype "bidirectional"))
      (node (ref "U2") (pin "3") (pinfunction "WP#/IO2_3") (pintype "bidirectional"))
    )
    (net (code "48") (name "QSPI_DATA[3]") (class "Default")
      (node (ref "U$2") (pin "20") (pinfunction "PA11/I11/AIN11/SERCOM0+2.3/I2SDO_20") (pintype "bidirectional"))
      (node (ref "U2") (pin "7") (pinfunction "HOLD#/IO3_7") (pintype "bidirectional"))
    )
    (net (code "49") (name "QSPI_SCK") (class "Default")
      (node (ref "U$2") (pin "23") (pinfunction "PB10/I10/SERCOM4.2/I2SDI_23") (pintype "bidirectional"))
      (node (ref "U2") (pin "6") (pinfunction "SCK_6") (pintype "bidirectional"))
    )
    (net (code "50") (name "RXD") (class "Default")
      (node (ref "U$2") (pin "26") (pinfunction "PB13/I13/SERCOM4.1/I2SMCK1_26") (pintype "bidirectional"))
      (node (ref "U3") (pin "22") (pinfunction "UART_TXD/GPIO1_22") (pintype "bidirectional"))
    )
    (net (code "51") (name "SCK") (class "Default")
      (node (ref "U$2") (pin "30") (pinfunction "PA13/I13/I2C/SERCOM2.1+4.0_30") (pintype "bidirectional"))
      (node (ref "U3") (pin "29") (pinfunction "SPIV_CLK/GPIO18_29") (pintype "bidirectional"))
      (node (ref "X1") (pin "5") (pinfunction "SCLK_5") (pintype "input"))
    )
    (net (code "52") (name "SCL") (class "Default")
      (node (ref "I2C") (pin "4") (pinfunction "SCL_4") (pintype "passive"))
      (node (ref "Q4") (pin "3") (pinfunction "D_3") (pintype "bidirectional"))
      (node (ref "R4") (pin "5") (pinfunction "2_5") (pintype "passive"))
    )
    (net (code "53") (name "SCL_3V") (class "Default")
      (node (ref "IC3") (pin "6") (pinfunction "SCL_6") (pintype "bidirectional"))
      (node (ref "Q4") (pin "4") (pinfunction "S_4") (pintype "bidirectional"))
      (node (ref "R4") (pin "6") (pinfunction "2_6") (pintype "passive"))
      (node (ref "U$2") (pin "64") (pinfunction "PB03/I3/AIN15/SERCOM5.1_64") (pintype "bidirectional"))
    )
    (net (code "54") (name "SDA") (class "Default")
      (node (ref "I2C") (pin "3") (pinfunction "SDA_3") (pintype "passive"))
      (node (ref "Q4") (pin "6") (pinfunction "D_6") (pintype "bidirectional"))
      (node (ref "R4") (pin "8") (pinfunction "2_8") (pintype "passive"))
    )
    (net (code "55") (name "SDA_3V") (class "Default")
      (node (ref "IC3") (pin "5") (pinfunction "SDA_5") (pintype "bidirectional"))
      (node (ref "Q4") (pin "1") (pinfunction "S_1") (pintype "bidirectional"))
      (node (ref "R4") (pin "7") (pinfunction "2_7") (pintype "passive"))
      (node (ref "U$2") (pin "63") (pinfunction "PB02/I2/AIN14/SERCOM5.0_63") (pintype "bidirectional"))
    )
    (net (code "56") (name "SD_CS") (class "Default")
      (node (ref "R18") (pin "2") (pinfunction "2_2") (pintype "passive"))
      (node (ref "U$2") (pin "59") (pinfunction "PB30/I14/SERCOM5.1/SWO_59") (pintype "bidirectional"))
      (node (ref "X1") (pin "2") (pinfunction "CS_2") (pintype "input"))
    )
    (net (code "57") (name "SPK_SD") (class "Default")
      (node (ref "IC2") (pin "4") (pinfunction "/SD_4") (pintype "input"))
      (node (ref "R22") (pin "2") (pinfunction "2_2") (pintype "passive"))
      (node (ref "U$2") (pin "51") (pinfunction "PA27/I11_51") (pintype "bidirectional"))
    )
    (net (code "58") (name "SWCLK") (class "Default")
      (node (ref "TP8") (pin "P$1") (pinfunction "P$1_P$1") (pintype "bidirectional"))
      (node (ref "U$2") (pin "57") (pinfunction "PA30/I14/SERCOM1.2/SWCLK_57") (pintype "bidirectional"))
      (node (ref "X3") (pin "4") (pinfunction "SWDCLK_4") (pintype "bidirectional"))
    )
    (net (code "59") (name "SWDIO") (class "Default")
      (node (ref "TP7") (pin "P$1") (pinfunction "P$1_P$1") (pintype "bidirectional"))
      (node (ref "U$2") (pin "58") (pinfunction "PA31/I15/SERCOM1.3/SWDIO_58") (pintype "bidirectional"))
      (node (ref "X3") (pin "2") (pinfunction "SWDIO_2") (pintype "bidirectional"))
    )
    (net (code "60") (name "TFT_BACKLITE") (class "Default")
      (node (ref "R5") (pin "1") (pinfunction "1_1") (pintype "passive"))
      (node (ref "U$2") (pin "60") (pinfunction "PB31/I15/SERCOM5.0_60") (pintype "bidirectional"))
    )
    (net (code "61") (name "TFT_CS") (class "Default")
      (node (ref "R20") (pin "2") (pinfunction "2_2") (pintype "passive"))
      (node (ref "U$2") (pin "9") (pinfunction "PB06/I6/AIN8_9") (pintype "bidirectional"))
      (node (ref "U$55") (pin "38") (pinfunction "#CS_38") (pintype "bidirectional"))
    )
    (net (code "62") (name "TFT_RD") (class "Default")
      (node (ref "U$2") (pin "5") (pinfunction "PB04/I4/AIN6_5") (pintype "bidirectional"))
      (node (ref "U$55") (pin "35") (pinfunction "#RD_35") (pintype "bidirectional"))
    )
    (net (code "63") (name "TFT_RESET") (class "Default")
      (node (ref "U$2") (pin "1") (pinfunction "PA00/EINT0/SERCOM1.0_1") (pintype "bidirectional"))
      (node (ref "U$55") (pin "10") (pinfunction "RESET_10") (pintype "bidirectional"))
    )
    (net (code "64") (name "TFT_RS") (class "Default")
      (node (ref "U$2") (pin "6") (pinfunction "PB05/I5/AIN7_6") (pintype "bidirectional"))
      (node (ref "U$55") (pin "37") (pinfunction "RS_37") (pintype "bidirectional"))
    )
    (net (code "65") (name "TFT_TE") (class "Default")
      (node (ref "U$2") (pin "10") (pinfunction "PB07/I7/AIN9_10") (pintype "bidirectional"))
      (node (ref "U$55") (pin "39") (pinfunction "TE_39") (pintype "bidirectional"))
    )
    (net (code "66") (name "TFT_WR") (class "Default")
      (node (ref "U$2") (pin "12") (pinfunction "PB09/I9/AIN3/SERCOM4.1_12") (pintype "bidirectional"))
      (node (ref "U$55") (pin "36") (pinfunction "#WR_36") (pintype "bidirectional"))
    )
    (net (code "67") (name "TOUCH_XL") (class "Default")
      (node (ref "U$2") (pin "62") (pinfunction "PB01/I1/AIN13/SERCOM5.3_62") (pintype "bidirectional"))
      (node (ref "U$55") (pin "46") (pinfunction "XL_46") (pintype "bidirectional"))
    )
    (net (code "68") (name "TOUCH_XR") (class "Default")
      (node (ref "U$2") (pin "11") (pinfunction "PB08/I8/AIN2/SERCOM4.0_11") (pintype "bidirectional"))
      (node (ref "U$55") (pin "44") (pinfunction "XR_44") (pintype "bidirectional"))
    )
    (net (code "69") (name "TOUCH_YD") (class "Default")
      (node (ref "U$2") (pin "61") (pinfunction "PB00/I0/AIN12/SERCOM5.2_61") (pintype "bidirectional"))
      (node (ref "U$55") (pin "45") (pinfunction "YD_45") (pintype "bidirectional"))
    )
    (net (code "70") (name "TOUCH_YU") (class "Default")
      (node (ref "U$2") (pin "15") (pinfunction "PA06/I6/VREFC/AIN6/SERCOM0.2_15") (pintype "bidirectional"))
      (node (ref "U$55") (pin "47") (pinfunction "YU_47") (pintype "bidirectional"))
    )
    (net (code "71") (name "TXD") (class "Default")
      (node (ref "U$2") (pin "25") (pinfunction "PB12/I12/SERCOM4.0/I2SCK1_25") (pintype "bidirectional"))
      (node (ref "U3") (pin "23") (pinfunction "UART_RXD/GPIO3_23") (pintype "bidirectional"))
    )
    (net (code "72") (name "VBUS") (class "Default")
      (node (ref "PTC1") (pin "2") (pinfunction "2_2") (pintype "passive"))
      (node (ref "X4") (pin "VBUS") (pinfunction "VBUS_VBUS") (pintype "power_in"))
    )
    (net (code "73") (name "VCC") (class "Default")
      (node (ref "C7") (pin "1") (pinfunction "1_1") (pintype "passive"))
      (node (ref "I2C") (pin "2") (pinfunction "V+_2") (pintype "passive"))
      (node (ref "NEOPIX") (pin "2") (pinfunction "2_2") (pintype "passive"))
      (node (ref "R4") (pin "1") (pinfunction "1_1") (pintype "passive"))
      (node (ref "R4") (pin "4") (pinfunction "1_4") (pintype "passive"))
      (node (ref "SENSE") (pin "2") (pinfunction "2_2") (pintype "passive"))
      (node (ref "SJ1") (pin "2") (pinfunction "2_2") (pintype "passive"))
    )
    (net (code "74") (name "unconnected-(LED1-DO-Pad3)") (class "Default")
      (node (ref "LED1") (pin "3") (pinfunction "DO_3") (pintype "output"))
    )
    (net (code "75") (name "unconnected-(U$2C-VSW-Pad55)") (class "Default")
      (node (ref "U$2") (pin "55") (pinfunction "VSW_55") (pintype "bidirectional"))
    )
    (net (code "76") (name "unconnected-(U$55-DB8-Pad24)") (class "Default")
      (node (ref "U$55") (pin "24") (pinfunction "DB8_24") (pintype "bidirectional"))
    )
    (net (code "77") (name "unconnected-(U$55-DB9-Pad23)") (class "Default")
      (node (ref "U$55") (pin "23") (pinfunction "DB9_23") (pintype "bidirectional"))
    )
    (net (code "78") (name "unconnected-(U$55-DB10-Pad22)") (class "Default")
      (node (ref "U$55") (pin "22") (pinfunction "DB10_22") (pintype "bidirectional"))
    )
    (net (code "79") (name "unconnected-(U$55-DB11-Pad21)") (class "Default")
      (node (ref "U$55") (pin "21") (pinfunction "DB11_21") (pintype "bidirectional"))
    )
    (net (code "80") (name "unconnected-(U$55-DB12-Pad20)") (class "Default")
      (node (ref "U$55") (pin "20") (pinfunction "DB12_20") (pintype "bidirectional"))
    )
    (net (code "81") (name "unconnected-(U$55-DB13-Pad19)") (class "Default")
      (node (ref "U$55") (pin "19") (pinfunction "DB13_19") (pintype "bidirectional"))
    )
    (net (code "82") (name "unconnected-(U$55-DB14-Pad18)") (class "Default")
      (node (ref "U$55") (pin "18") (pinfunction "DB14_18") (pintype "bidirectional"))
    )
    (net (code "83") (name "unconnected-(U$55-DB15-Pad17)") (class "Default")
      (node (ref "U$55") (pin "17") (pinfunction "DB15_17") (pintype "bidirectional"))
    )
    (net (code "84") (name "unconnected-(U$55-DB16-Pad16)") (class "Default")
      (node (ref "U$55") (pin "16") (pinfunction "DB16_16") (pintype "bidirectional"))
    )
    (net (code "85") (name "unconnected-(U$55-DB17-Pad15)") (class "Default")
      (node (ref "U$55") (pin "15") (pinfunction "DB17_15") (pintype "bidirectional"))
    )
    (net (code "86") (name "unconnected-(U$55-DE-Pad14)") (class "Default")
      (node (ref "U$55") (pin "14") (pinfunction "DE_14") (pintype "bidirectional"))
    )
    (net (code "87") (name "unconnected-(U$55-DOTCLK-Pad13)") (class "Default")
      (node (ref "U$55") (pin "13") (pinfunction "DOTCLK_13") (pintype "bidirectional"))
    )
    (net (code "88") (name "unconnected-(U$55-HSYNC-Pad12)") (class "Default")
      (node (ref "U$55") (pin "12") (pinfunction "HSYNC_12") (pintype "bidirectional"))
    )
    (net (code "89") (name "unconnected-(U$55-SDI-Pad34)") (class "Default")
      (node (ref "U$55") (pin "34") (pinfunction "SDI_34") (pintype "bidirectional"))
    )
    (net (code "90") (name "unconnected-(U$55-SDO-Pad33)") (class "Default")
      (node (ref "U$55") (pin "33") (pinfunction "SDO_33") (pintype "bidirectional"))
    )
    (net (code "91") (name "unconnected-(U$55-VSYNC-Pad11)") (class "Default")
      (node (ref "U$55") (pin "11") (pinfunction "VSYNC_11") (pintype "bidirectional"))
    )
    (net (code "92") (name "unconnected-(U1-P4-Pad4)") (class "Default")
      (node (ref "U1") (pin "4") (pinfunction "P4_4") (pintype "bidirectional"))
    )
    (net (code "93") (name "unconnected-(U3A-ADC2{slash}GPIO34-Pad2)") (class "Default")
      (node (ref "U3") (pin "2") (pinfunction "ADC2/GPIO34_2") (pintype "bidirectional"))
    )
    (net (code "94") (name "unconnected-(U3A-ADC3{slash}GPIO39-Pad3)") (class "Default")
      (node (ref "U3") (pin "3") (pinfunction "ADC3/GPIO39_3") (pintype "bidirectional"))
    )
    (net (code "95") (name "unconnected-(U3A-ADC4{slash}GPIO36-Pad4)") (class "Default")
      (node (ref "U3") (pin "4") (pinfunction "ADC4/GPIO36_4") (pintype "bidirectional"))
    )
    (net (code "96") (name "unconnected-(U3A-ADC34{slash}GPI35-Pad34)") (class "Default")
      (node (ref "U3") (pin "34") (pinfunction "ADC34/GPI35_34") (pintype "bidirectional"))
    )
    (net (code "97") (name "unconnected-(U3A-ANT-Pad13)") (class "Default")
      (node (ref "U3") (pin "13") (pinfunction "ANT_13") (pintype "bidirectional"))
    )
    (net (code "98") (name "unconnected-(U3A-GPIO12-Pad36)") (class "Default")
      (node (ref "U3") (pin "36") (pinfunction "GPIO12_36") (pintype "bidirectional"))
    )
    (net (code "99") (name "unconnected-(U3A-JTCLK{slash}GPIO13-Pad35)") (class "Default")
      (node (ref "U3") (pin "35") (pinfunction "JTCLK/GPIO13_35") (pintype "bidirectional"))
    )
    (net (code "100") (name "unconnected-(U3A-JTDO{slash}GPIO15-Pad32)") (class "Default")
      (node (ref "U3") (pin "32") (pinfunction "JTDO/GPIO15_32") (pintype "bidirectional"))
    )
    (net (code "101") (name "unconnected-(U3A-LPO_IN{slash}GPIO32-Pad5)") (class "Default")
      (node (ref "U3") (pin "5") (pinfunction "LPO_IN/GPIO32_5") (pintype "bidirectional"))
    )
    (net (code "102") (name "unconnected-(U3A-RMII_CRSDV{slash}GPIO27-Pad18)") (class "Default")
      (node (ref "U3") (pin "18") (pinfunction "RMII_CRSDV/GPIO27_18") (pintype "bidirectional"))
    )
    (net (code "103") (name "unconnected-(U3A-RMII_MDCLK{slash}GPIO2-Pad25)") (class "Default")
      (node (ref "U3") (pin "25") (pinfunction "RMII_MDCLK/GPIO2_25") (pintype "bidirectional"))
    )
    (net (code "104") (name "unconnected-(U3A-RMII_MDIO{slash}GPIO4-Pad24)") (class "Default")
      (node (ref "U3") (pin "24") (pinfunction "RMII_MDIO/GPIO4_24") (pintype "bidirectional"))
    )
    (net (code "105") (name "unconnected-(U3A-RMII_RXD0{slash}DAC16{slash}GPIO25-Pad16)") (class "Default")
      (node (ref "U3") (pin "16") (pinfunction "RMII_RXD0/DAC16/GPIO25_16") (pintype "bidirectional"))
    )
    (net (code "106") (name "unconnected-(U3A-RMII_RXD1{slash}DAC17{slash}GPIO26-Pad17)") (class "Default")
      (node (ref "U3") (pin "17") (pinfunction "RMII_RXD1/DAC17/GPIO26_17") (pintype "bidirectional"))
    )
    (net (code "107") (name "unconnected-(U3A-SPIV_HD{slash}RMII_TXEN{slash}GPIO21-Pad8)") (class "Default")
      (node (ref "U3") (pin "8") (pinfunction "SPIV_HD/RMII_TXEN/GPIO21_8") (pintype "bidirectional"))
    )
    (net (code "108") (name "unconnected-(U3A-UART_RTS{slash}RMII_TXD1{slash}SPIV_WP{slash}GPIO22-Pad20)") (class "Default")
      (node (ref "U3") (pin "20") (pinfunction "UART_RTS/RMII_TXD1/SPIV_WP/GPIO22_20") (pintype "bidirectional"))
    )
    (net (code "109") (name "unconnected-(X1-CARD_DETECT-PadCD1)") (class "Default")
      (node (ref "X1") (pin "CD1") (pinfunction "CARD_DETECT_CD1") (pintype "passive"))
    )
    (net (code "110") (name "unconnected-(X1-DAT1-Pad8)") (class "Default")
      (node (ref "X1") (pin "8") (pinfunction "DAT1_8") (pintype "bidirectional"))
    )
    (net (code "111") (name "unconnected-(X1-DAT2-Pad1)") (class "Default")
      (node (ref "X1") (pin "1") (pinfunction "DAT2_1") (pintype "bidirectional"))
    )
    (net (code "112") (name "unconnected-(X3-SWO-Pad6)") (class "Default")
      (node (ref "X3") (pin "6") (pinfunction "SWO_6") (pintype "bidirectional"))
    )
    (net (code "113") (name "unconnected-(X3-TDI-Pad8)") (class "Default")
      (node (ref "X3") (pin "8") (pinfunction "TDI_8") (pintype "bidirectional"))
    )
    (net (code "114") (name "unconnected-(X4-PadID)") (class "Default")
      (node (ref "X4") (pin "ID") (pinfunction "ID_ID") (pintype "bidirectional"))
    )
    (net (code "115") (name "~{RESET}") (class "Default")
      (node (ref "C17") (pin "2") (pinfunction "2_2") (pintype "passive"))
      (node (ref "R6") (pin "2") (pinfunction "2_2") (pintype "passive"))
      (node (ref "RESET") (pin "B") (pinfunction "S_B") (pintype "passive"))
      (node (ref "RESET") (pin "B'") (pinfunction "S1_B'") (pintype "passive"))
      (node (ref "TP9") (pin "P$1") (pinfunction "P$1_P$1") (pintype "bidirectional"))
      (node (ref "U$2") (pin "52") (pinfunction "~{RESET}_52") (pintype "bidirectional"))
      (node (ref "X3") (pin "10") (pinfunction "NRESET_10") (pintype "bidirectional"))
    )
  )
)
